# main_board.net
KiCad netlist of a schematic drawn in EAGLE
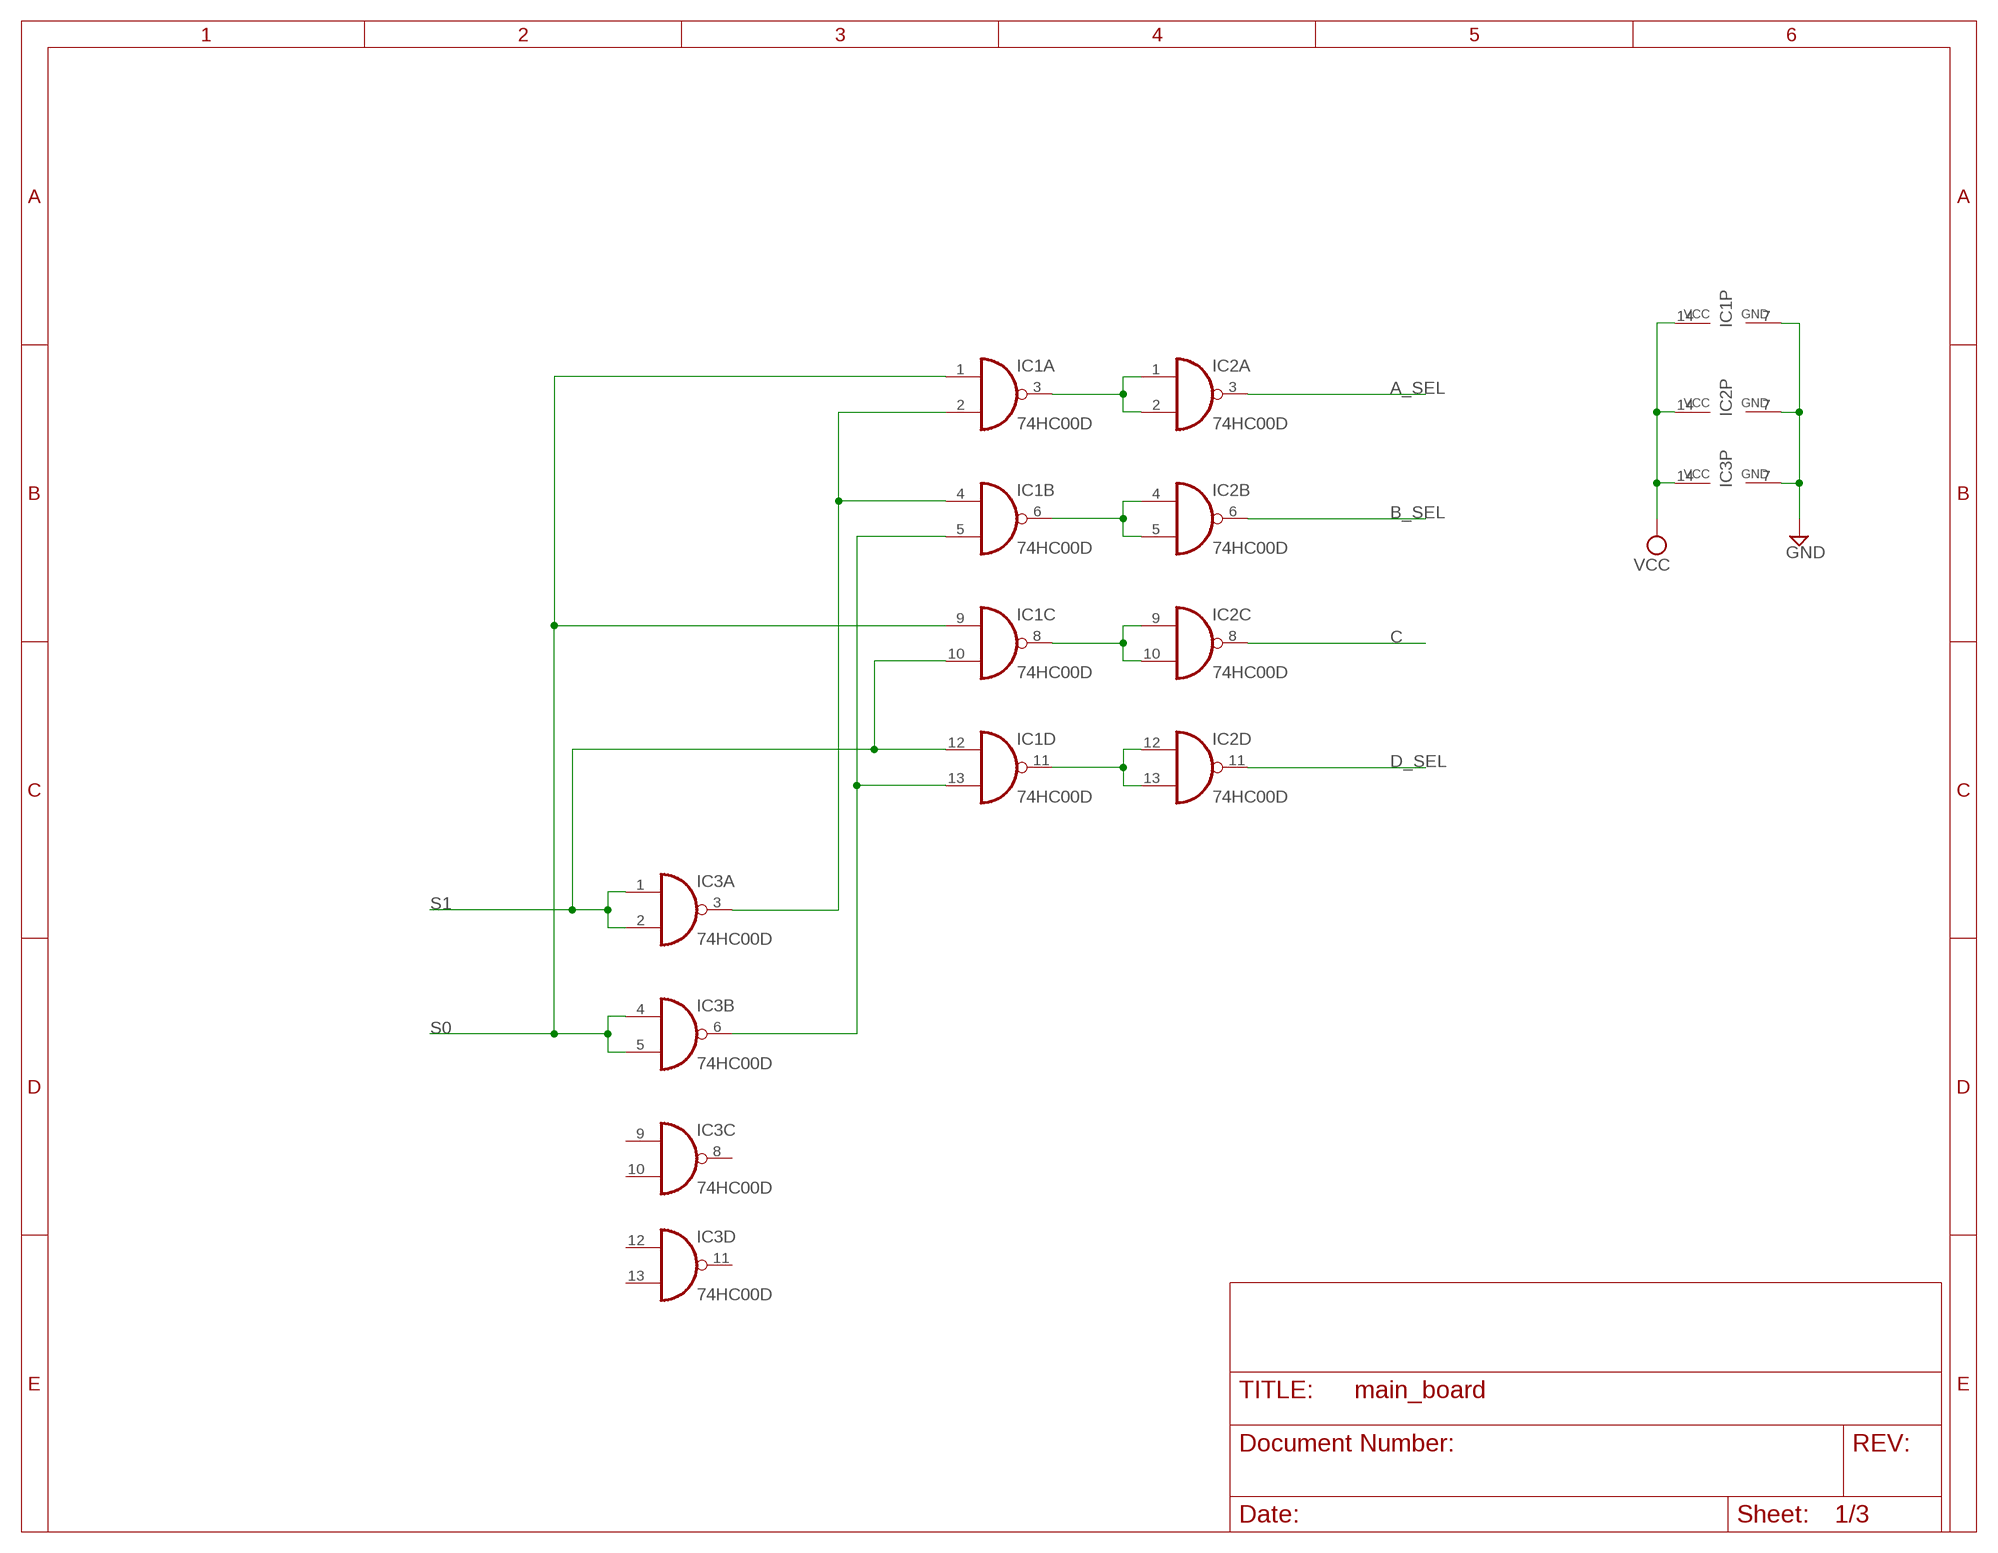
[diagram p0: schematic, sheet 1]
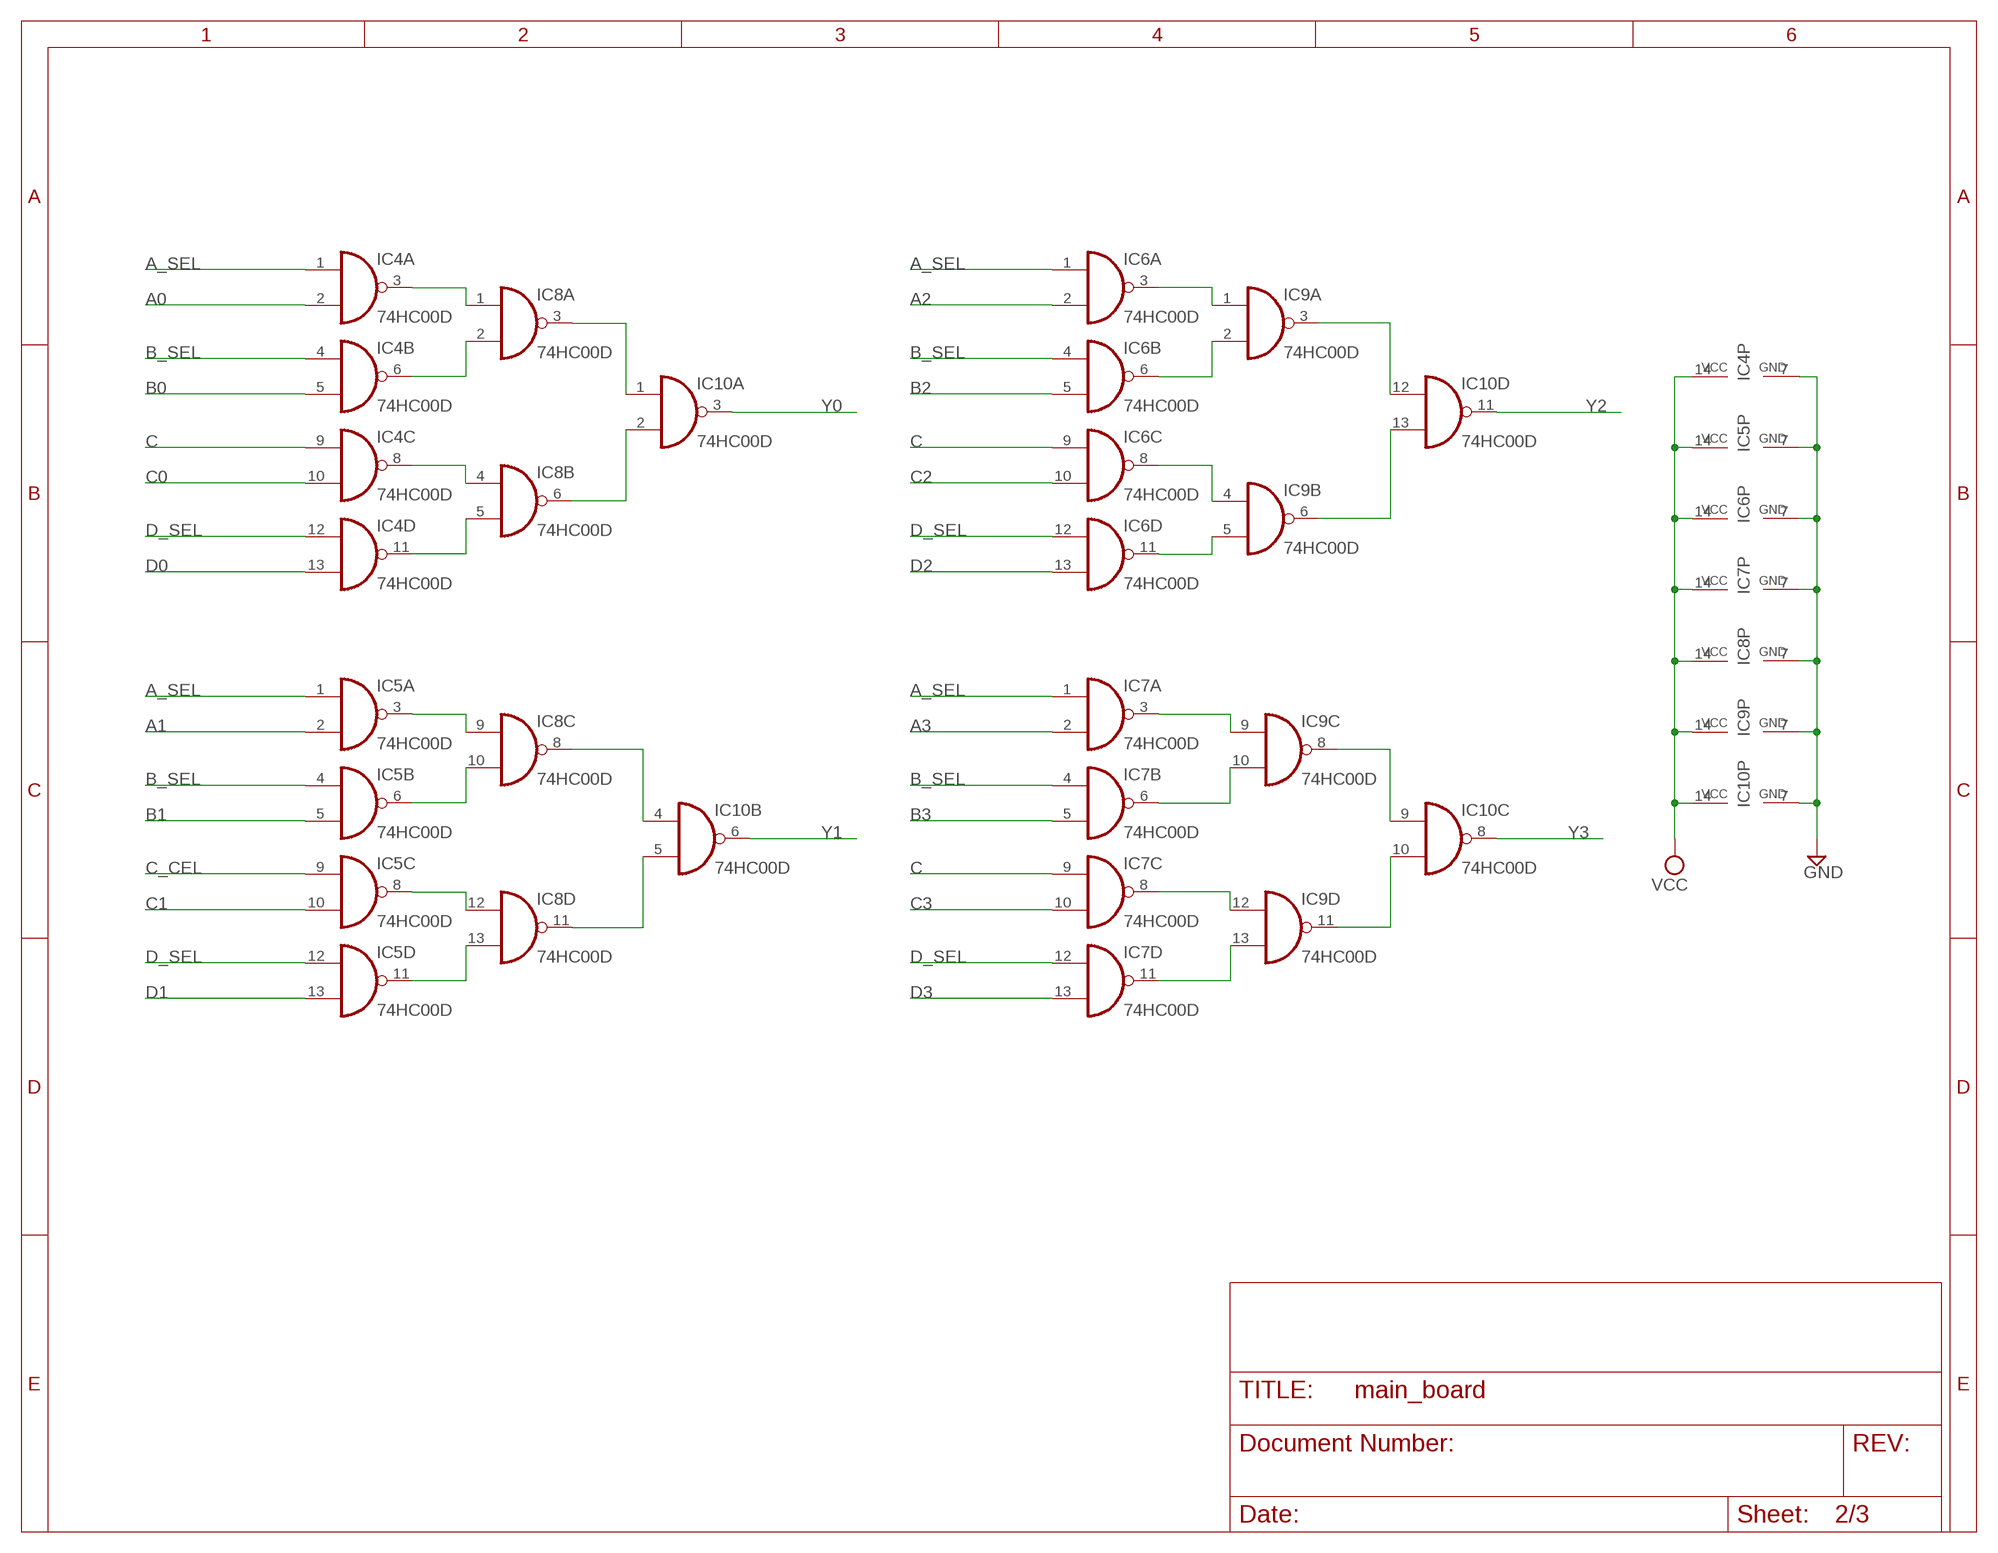
[diagram p1: schematic, sheet 2]
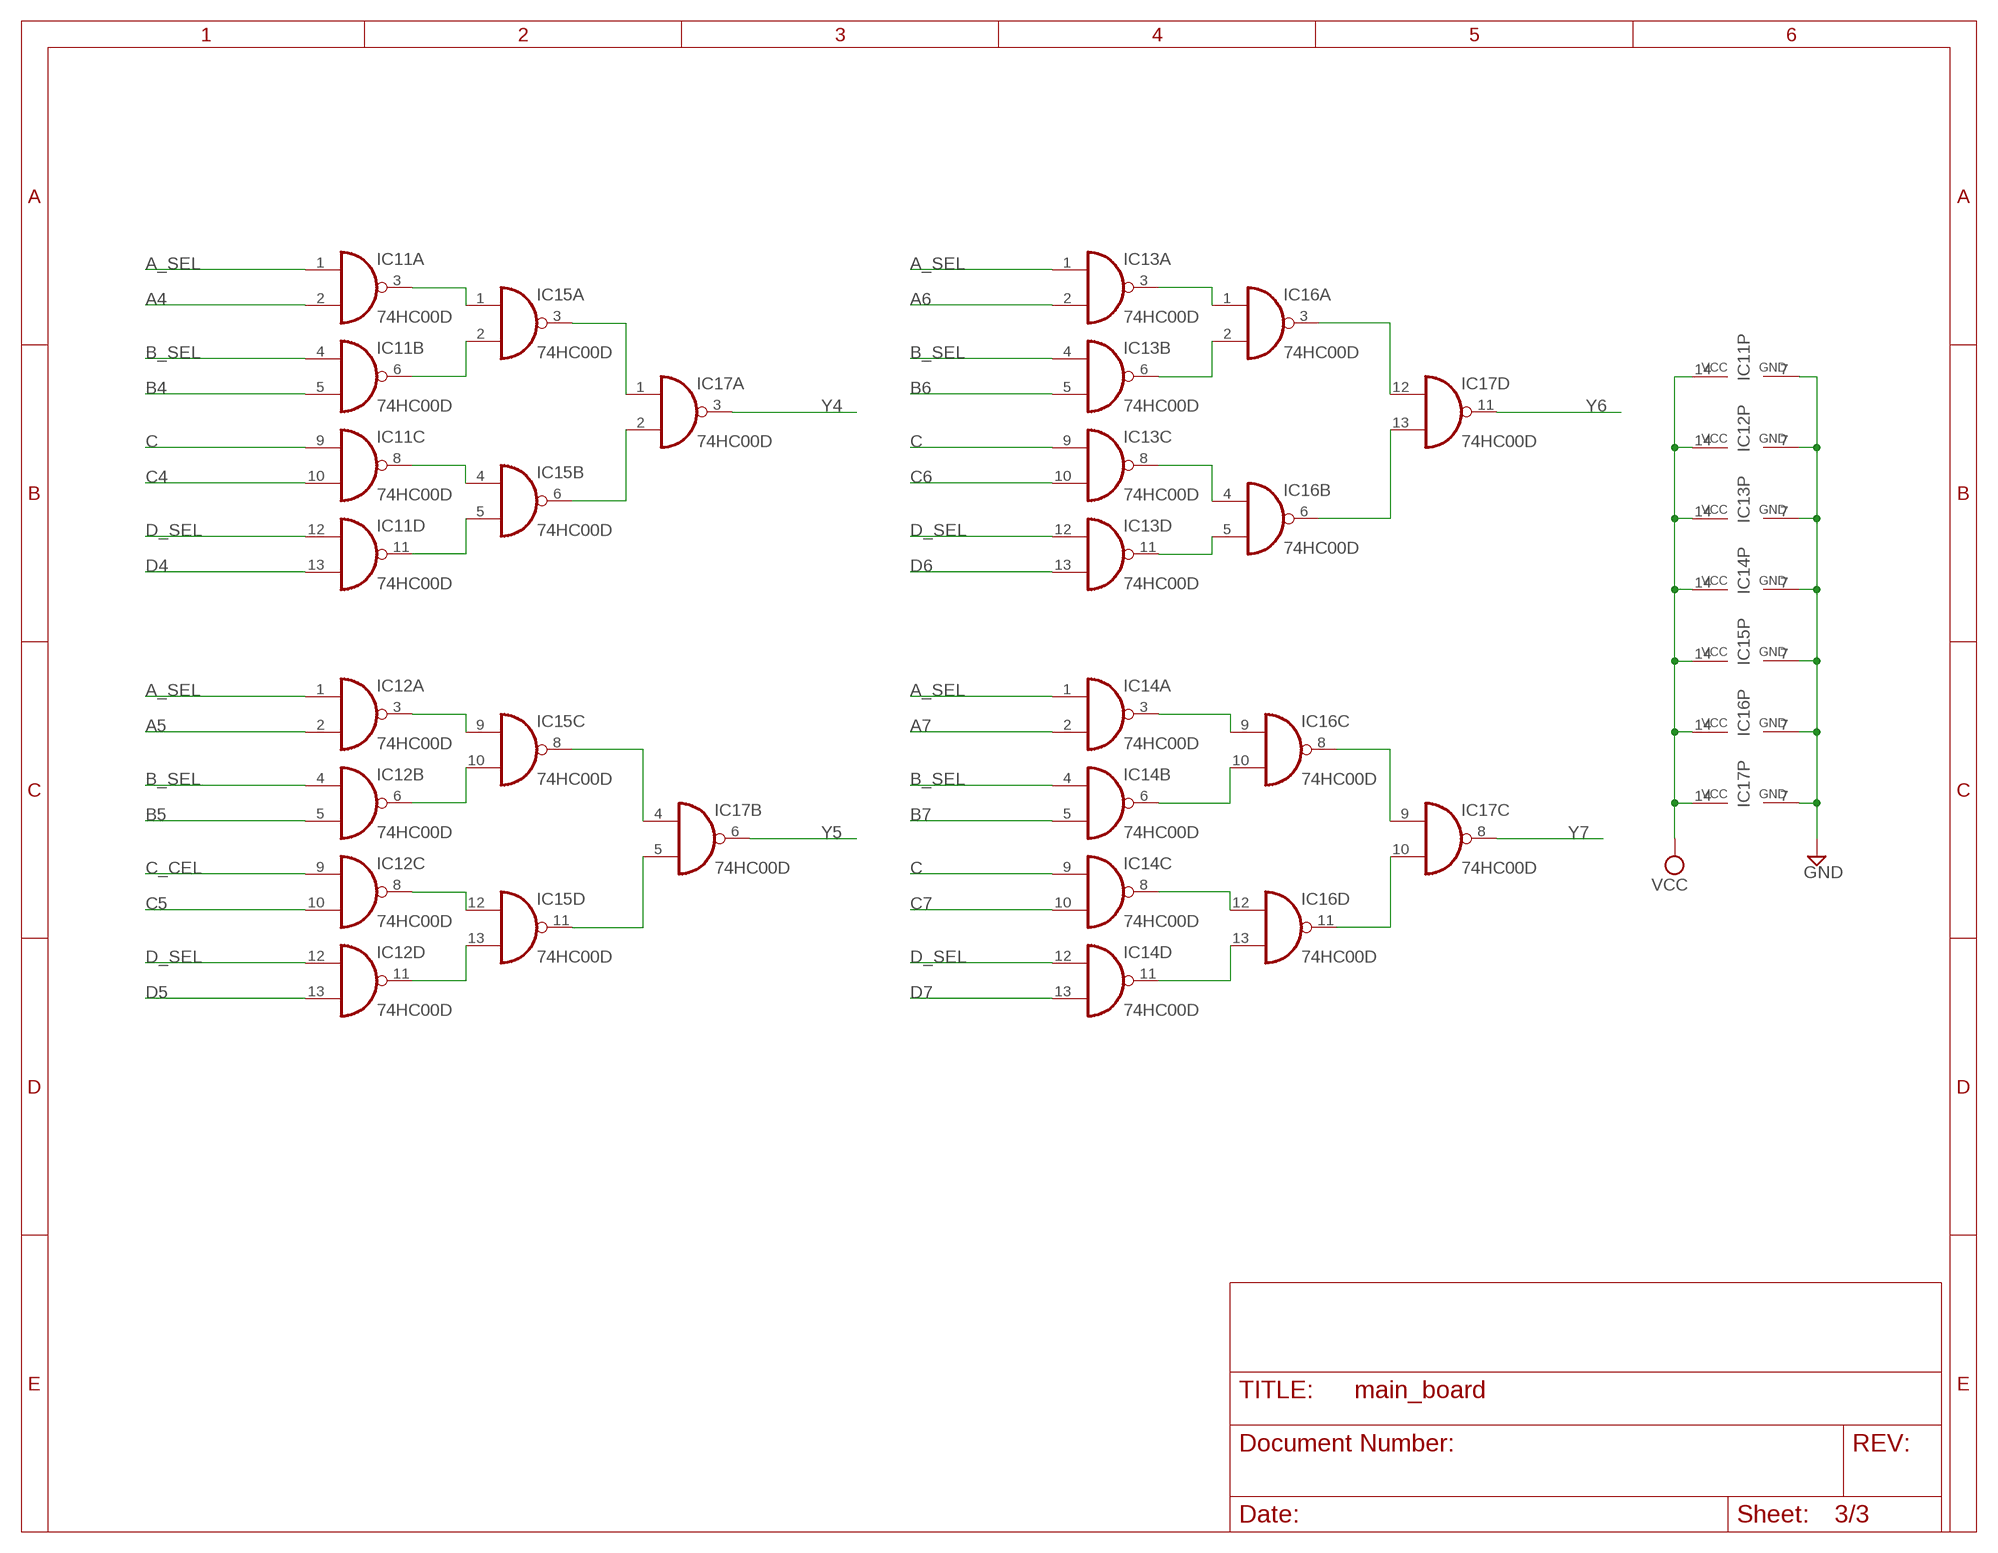
[diagram p2: schematic, sheet 3]

(export (version "E")
  (design (tool "Eeschema 10.0.6"))
  (components
    (comp (ref "IC4")
      (value "74HC00D")
      (footprint "eagle-import:SO14")
      (libsource (lib "eagle-import") (part "7400DHC"))
    )
    (comp (ref "IC5")
      (value "74HC00D")
      (footprint "eagle-import:SO14")
      (libsource (lib "eagle-import") (part "7400DHC"))
    )
    (comp (ref "IC6")
      (value "74HC00D")
      (footprint "eagle-import:SO14")
      (libsource (lib "eagle-import") (part "7400DHC"))
    )
    (comp (ref "IC7")
      (value "74HC00D")
      (footprint "eagle-import:SO14")
      (libsource (lib "eagle-import") (part "7400DHC"))
    )
    (comp (ref "IC8")
      (value "74HC00D")
      (footprint "eagle-import:SO14")
      (libsource (lib "eagle-import") (part "7400DHC"))
    )
    (comp (ref "IC9")
      (value "74HC00D")
      (footprint "eagle-import:SO14")
      (libsource (lib "eagle-import") (part "7400DHC"))
    )
    (comp (ref "IC10")
      (value "74HC00D")
      (footprint "eagle-import:SO14")
      (libsource (lib "eagle-import") (part "7400DHC"))
    )
    (comp (ref "IC1")
      (value "74HC00D")
      (footprint "eagle-import:SO14")
      (libsource (lib "eagle-import") (part "7400DHC"))
    )
    (comp (ref "IC2")
      (value "74HC00D")
      (footprint "eagle-import:SO14")
      (libsource (lib "eagle-import") (part "7400DHC"))
    )
    (comp (ref "IC3")
      (value "74HC00D")
      (footprint "eagle-import:SO14")
      (libsource (lib "eagle-import") (part "7400DHC"))
    )
    (comp (ref "IC11")
      (value "74HC00D")
      (footprint "eagle-import:SO14")
      (libsource (lib "eagle-import") (part "7400DHC"))
    )
    (comp (ref "IC12")
      (value "74HC00D")
      (footprint "eagle-import:SO14")
      (libsource (lib "eagle-import") (part "7400DHC"))
    )
    (comp (ref "IC13")
      (value "74HC00D")
      (footprint "eagle-import:SO14")
      (libsource (lib "eagle-import") (part "7400DHC"))
    )
    (comp (ref "IC14")
      (value "74HC00D")
      (footprint "eagle-import:SO14")
      (libsource (lib "eagle-import") (part "7400DHC"))
    )
    (comp (ref "IC15")
      (value "74HC00D")
      (footprint "eagle-import:SO14")
      (libsource (lib "eagle-import") (part "7400DHC"))
    )
    (comp (ref "IC16")
      (value "74HC00D")
      (footprint "eagle-import:SO14")
      (libsource (lib "eagle-import") (part "7400DHC"))
    )
    (comp (ref "IC17")
      (value "74HC00D")
      (footprint "eagle-import:SO14")
      (libsource (lib "eagle-import") (part "7400DHC"))
    )
  )
  (nets
    (net (code "1") (name "A0") (class "Default")
      (node (ref "IC4") (pin "2") (pinfunction "I1_2") (pintype "input"))
    )
    (net (code "2") (name "A1") (class "Default")
      (node (ref "IC5") (pin "2") (pinfunction "I1_2") (pintype "input"))
    )
    (net (code "3") (name "A2") (class "Default")
      (node (ref "IC6") (pin "2") (pinfunction "I1_2") (pintype "input"))
    )
    (net (code "4") (name "A3") (class "Default")
      (node (ref "IC7") (pin "2") (pinfunction "I1_2") (pintype "input"))
    )
    (net (code "5") (name "A4") (class "Default")
      (node (ref "IC11") (pin "2") (pinfunction "I1_2") (pintype "input"))
    )
    (net (code "6") (name "A5") (class "Default")
      (node (ref "IC12") (pin "2") (pinfunction "I1_2") (pintype "input"))
    )
    (net (code "7") (name "A6") (class "Default")
      (node (ref "IC13") (pin "2") (pinfunction "I1_2") (pintype "input"))
    )
    (net (code "8") (name "A7") (class "Default")
      (node (ref "IC14") (pin "2") (pinfunction "I1_2") (pintype "input"))
    )
    (net (code "9") (name "A_SEL") (class "Default")
      (node (ref "IC11") (pin "1") (pinfunction "I0_1") (pintype "input"))
      (node (ref "IC12") (pin "1") (pinfunction "I0_1") (pintype "input"))
      (node (ref "IC13") (pin "1") (pinfunction "I0_1") (pintype "input"))
      (node (ref "IC14") (pin "1") (pinfunction "I0_1") (pintype "input"))
      (node (ref "IC2") (pin "3") (pinfunction "O_3") (pintype "output"))
      (node (ref "IC4") (pin "1") (pinfunction "I0_1") (pintype "input"))
      (node (ref "IC5") (pin "1") (pinfunction "I0_1") (pintype "input"))
      (node (ref "IC6") (pin "1") (pinfunction "I0_1") (pintype "input"))
      (node (ref "IC7") (pin "1") (pinfunction "I0_1") (pintype "input"))
    )
    (net (code "10") (name "B0") (class "Default")
      (node (ref "IC4") (pin "5") (pinfunction "I1_5") (pintype "input"))
    )
    (net (code "11") (name "B1") (class "Default")
      (node (ref "IC5") (pin "5") (pinfunction "I1_5") (pintype "input"))
    )
    (net (code "12") (name "B2") (class "Default")
      (node (ref "IC6") (pin "5") (pinfunction "I1_5") (pintype "input"))
    )
    (net (code "13") (name "B3") (class "Default")
      (node (ref "IC7") (pin "5") (pinfunction "I1_5") (pintype "input"))
    )
    (net (code "14") (name "B4") (class "Default")
      (node (ref "IC11") (pin "5") (pinfunction "I1_5") (pintype "input"))
    )
    (net (code "15") (name "B5") (class "Default")
      (node (ref "IC12") (pin "5") (pinfunction "I1_5") (pintype "input"))
    )
    (net (code "16") (name "B6") (class "Default")
      (node (ref "IC13") (pin "5") (pinfunction "I1_5") (pintype "input"))
    )
    (net (code "17") (name "B7") (class "Default")
      (node (ref "IC14") (pin "5") (pinfunction "I1_5") (pintype "input"))
    )
    (net (code "18") (name "B_SEL") (class "Default")
      (node (ref "IC11") (pin "4") (pinfunction "I0_4") (pintype "input"))
      (node (ref "IC12") (pin "4") (pinfunction "I0_4") (pintype "input"))
      (node (ref "IC13") (pin "4") (pinfunction "I0_4") (pintype "input"))
      (node (ref "IC14") (pin "4") (pinfunction "I0_4") (pintype "input"))
      (node (ref "IC2") (pin "6") (pinfunction "O_6") (pintype "output"))
      (node (ref "IC4") (pin "4") (pinfunction "I0_4") (pintype "input"))
      (node (ref "IC5") (pin "4") (pinfunction "I0_4") (pintype "input"))
      (node (ref "IC6") (pin "4") (pinfunction "I0_4") (pintype "input"))
      (node (ref "IC7") (pin "4") (pinfunction "I0_4") (pintype "input"))
    )
    (net (code "19") (name "C") (class "Default")
      (node (ref "IC11") (pin "9") (pinfunction "I0_9") (pintype "input"))
      (node (ref "IC13") (pin "9") (pinfunction "I0_9") (pintype "input"))
      (node (ref "IC14") (pin "9") (pinfunction "I0_9") (pintype "input"))
      (node (ref "IC2") (pin "8") (pinfunction "O_8") (pintype "output"))
      (node (ref "IC4") (pin "9") (pinfunction "I0_9") (pintype "input"))
      (node (ref "IC6") (pin "9") (pinfunction "I0_9") (pintype "input"))
      (node (ref "IC7") (pin "9") (pinfunction "I0_9") (pintype "input"))
    )
    (net (code "20") (name "C0") (class "Default")
      (node (ref "IC4") (pin "10") (pinfunction "I1_10") (pintype "input"))
    )
    (net (code "21") (name "C1") (class "Default")
      (node (ref "IC5") (pin "10") (pinfunction "I1_10") (pintype "input"))
    )
    (net (code "22") (name "C2") (class "Default")
      (node (ref "IC6") (pin "10") (pinfunction "I1_10") (pintype "input"))
    )
    (net (code "23") (name "C3") (class "Default")
      (node (ref "IC7") (pin "10") (pinfunction "I1_10") (pintype "input"))
    )
    (net (code "24") (name "C4") (class "Default")
      (node (ref "IC11") (pin "10") (pinfunction "I1_10") (pintype "input"))
    )
    (net (code "25") (name "C5") (class "Default")
      (node (ref "IC12") (pin "10") (pinfunction "I1_10") (pintype "input"))
    )
    (net (code "26") (name "C6") (class "Default")
      (node (ref "IC13") (pin "10") (pinfunction "I1_10") (pintype "input"))
    )
    (net (code "27") (name "C7") (class "Default")
      (node (ref "IC14") (pin "10") (pinfunction "I1_10") (pintype "input"))
    )
    (net (code "28") (name "C_CEL") (class "Default")
      (node (ref "IC12") (pin "9") (pinfunction "I0_9") (pintype "input"))
      (node (ref "IC5") (pin "9") (pinfunction "I0_9") (pintype "input"))
    )
    (net (code "29") (name "D0") (class "Default")
      (node (ref "IC4") (pin "13") (pinfunction "I1_13") (pintype "input"))
    )
    (net (code "30") (name "D1") (class "Default")
      (node (ref "IC5") (pin "13") (pinfunction "I1_13") (pintype "input"))
    )
    (net (code "31") (name "D2") (class "Default")
      (node (ref "IC6") (pin "13") (pinfunction "I1_13") (pintype "input"))
    )
    (net (code "32") (name "D3") (class "Default")
      (node (ref "IC7") (pin "13") (pinfunction "I1_13") (pintype "input"))
    )
    (net (code "33") (name "D4") (class "Default")
      (node (ref "IC11") (pin "13") (pinfunction "I1_13") (pintype "input"))
    )
    (net (code "34") (name "D5") (class "Default")
      (node (ref "IC12") (pin "13") (pinfunction "I1_13") (pintype "input"))
    )
    (net (code "35") (name "D6") (class "Default")
      (node (ref "IC13") (pin "13") (pinfunction "I1_13") (pintype "input"))
    )
    (net (code "36") (name "D7") (class "Default")
      (node (ref "IC14") (pin "13") (pinfunction "I1_13") (pintype "input"))
    )
    (net (code "37") (name "D_SEL") (class "Default")
      (node (ref "IC11") (pin "12") (pinfunction "I0_12") (pintype "input"))
      (node (ref "IC12") (pin "12") (pinfunction "I0_12") (pintype "input"))
      (node (ref "IC13") (pin "12") (pinfunction "I0_12") (pintype "input"))
      (node (ref "IC14") (pin "12") (pinfunction "I0_12") (pintype "input"))
      (node (ref "IC2") (pin "11") (pinfunction "O_11") (pintype "output"))
      (node (ref "IC4") (pin "12") (pinfunction "I0_12") (pintype "input"))
      (node (ref "IC5") (pin "12") (pinfunction "I0_12") (pintype "input"))
      (node (ref "IC6") (pin "12") (pinfunction "I0_12") (pintype "input"))
      (node (ref "IC7") (pin "12") (pinfunction "I0_12") (pintype "input"))
    )
    (net (code "38") (name "GND") (class "Default")
      (node (ref "IC1") (pin "7") (pinfunction "GND_7") (pintype "power_in"))
      (node (ref "IC10") (pin "7") (pinfunction "GND_7") (pintype "power_in"))
      (node (ref "IC11") (pin "7") (pinfunction "GND_7") (pintype "power_in"))
      (node (ref "IC12") (pin "7") (pinfunction "GND_7") (pintype "power_in"))
      (node (ref "IC13") (pin "7") (pinfunction "GND_7") (pintype "power_in"))
      (node (ref "IC14") (pin "7") (pinfunction "GND_7") (pintype "power_in"))
      (node (ref "IC15") (pin "7") (pinfunction "GND_7") (pintype "power_in"))
      (node (ref "IC16") (pin "7") (pinfunction "GND_7") (pintype "power_in"))
      (node (ref "IC17") (pin "7") (pinfunction "GND_7") (pintype "power_in"))
      (node (ref "IC2") (pin "7") (pinfunction "GND_7") (pintype "power_in"))
      (node (ref "IC3") (pin "7") (pinfunction "GND_7") (pintype "power_in"))
      (node (ref "IC4") (pin "7") (pinfunction "GND_7") (pintype "power_in"))
      (node (ref "IC5") (pin "7") (pinfunction "GND_7") (pintype "power_in"))
      (node (ref "IC6") (pin "7") (pinfunction "GND_7") (pintype "power_in"))
      (node (ref "IC7") (pin "7") (pinfunction "GND_7") (pintype "power_in"))
      (node (ref "IC8") (pin "7") (pinfunction "GND_7") (pintype "power_in"))
      (node (ref "IC9") (pin "7") (pinfunction "GND_7") (pintype "power_in"))
    )
    (net (code "39") (name "Net-(IC1A-I1)") (class "Default")
      (node (ref "IC1") (pin "2") (pinfunction "I1_2") (pintype "input"))
      (node (ref "IC1") (pin "4") (pinfunction "I0_4") (pintype "input"))
      (node (ref "IC3") (pin "3") (pinfunction "O_3") (pintype "output"))
    )
    (net (code "40") (name "Net-(IC1A-O)") (class "Default")
      (node (ref "IC1") (pin "3") (pinfunction "O_3") (pintype "output"))
      (node (ref "IC2") (pin "1") (pinfunction "I0_1") (pintype "input"))
      (node (ref "IC2") (pin "2") (pinfunction "I1_2") (pintype "input"))
    )
    (net (code "41") (name "Net-(IC1B-I1)") (class "Default")
      (node (ref "IC1") (pin "13") (pinfunction "I1_13") (pintype "input"))
      (node (ref "IC1") (pin "5") (pinfunction "I1_5") (pintype "input"))
      (node (ref "IC3") (pin "6") (pinfunction "O_6") (pintype "output"))
    )
    (net (code "42") (name "Net-(IC1B-O)") (class "Default")
      (node (ref "IC1") (pin "6") (pinfunction "O_6") (pintype "output"))
      (node (ref "IC2") (pin "4") (pinfunction "I0_4") (pintype "input"))
      (node (ref "IC2") (pin "5") (pinfunction "I1_5") (pintype "input"))
    )
    (net (code "43") (name "Net-(IC1C-O)") (class "Default")
      (node (ref "IC1") (pin "8") (pinfunction "O_8") (pintype "output"))
      (node (ref "IC2") (pin "10") (pinfunction "I1_10") (pintype "input"))
      (node (ref "IC2") (pin "9") (pinfunction "I0_9") (pintype "input"))
    )
    (net (code "44") (name "Net-(IC1D-O)") (class "Default")
      (node (ref "IC1") (pin "11") (pinfunction "O_11") (pintype "output"))
      (node (ref "IC2") (pin "12") (pinfunction "I0_12") (pintype "input"))
      (node (ref "IC2") (pin "13") (pinfunction "I1_13") (pintype "input"))
    )
    (net (code "45") (name "Net-(IC4A-O)") (class "Default")
      (node (ref "IC4") (pin "3") (pinfunction "O_3") (pintype "output"))
      (node (ref "IC8") (pin "1") (pinfunction "I0_1") (pintype "input"))
    )
    (net (code "46") (name "Net-(IC4B-O)") (class "Default")
      (node (ref "IC4") (pin "6") (pinfunction "O_6") (pintype "output"))
      (node (ref "IC8") (pin "2") (pinfunction "I1_2") (pintype "input"))
    )
    (net (code "47") (name "Net-(IC4C-O)") (class "Default")
      (node (ref "IC4") (pin "8") (pinfunction "O_8") (pintype "output"))
      (node (ref "IC8") (pin "4") (pinfunction "I0_4") (pintype "input"))
    )
    (net (code "48") (name "Net-(IC4D-O)") (class "Default")
      (node (ref "IC4") (pin "11") (pinfunction "O_11") (pintype "output"))
      (node (ref "IC8") (pin "5") (pinfunction "I1_5") (pintype "input"))
    )
    (net (code "49") (name "Net-(IC5A-O)") (class "Default")
      (node (ref "IC5") (pin "3") (pinfunction "O_3") (pintype "output"))
      (node (ref "IC8") (pin "9") (pinfunction "I0_9") (pintype "input"))
    )
    (net (code "50") (name "Net-(IC5B-O)") (class "Default")
      (node (ref "IC5") (pin "6") (pinfunction "O_6") (pintype "output"))
      (node (ref "IC8") (pin "10") (pinfunction "I1_10") (pintype "input"))
    )
    (net (code "51") (name "Net-(IC5C-O)") (class "Default")
      (node (ref "IC5") (pin "8") (pinfunction "O_8") (pintype "output"))
      (node (ref "IC8") (pin "12") (pinfunction "I0_12") (pintype "input"))
    )
    (net (code "52") (name "Net-(IC5D-O)") (class "Default")
      (node (ref "IC5") (pin "11") (pinfunction "O_11") (pintype "output"))
      (node (ref "IC8") (pin "13") (pinfunction "I1_13") (pintype "input"))
    )
    (net (code "53") (name "Net-(IC6A-O)") (class "Default")
      (node (ref "IC6") (pin "3") (pinfunction "O_3") (pintype "output"))
      (node (ref "IC9") (pin "1") (pinfunction "I0_1") (pintype "input"))
    )
    (net (code "54") (name "Net-(IC6B-O)") (class "Default")
      (node (ref "IC6") (pin "6") (pinfunction "O_6") (pintype "output"))
      (node (ref "IC9") (pin "2") (pinfunction "I1_2") (pintype "input"))
    )
    (net (code "55") (name "Net-(IC6C-O)") (class "Default")
      (node (ref "IC6") (pin "8") (pinfunction "O_8") (pintype "output"))
      (node (ref "IC9") (pin "4") (pinfunction "I0_4") (pintype "input"))
    )
    (net (code "56") (name "Net-(IC6D-O)") (class "Default")
      (node (ref "IC6") (pin "11") (pinfunction "O_11") (pintype "output"))
      (node (ref "IC9") (pin "5") (pinfunction "I1_5") (pintype "input"))
    )
    (net (code "57") (name "Net-(IC7A-O)") (class "Default")
      (node (ref "IC7") (pin "3") (pinfunction "O_3") (pintype "output"))
      (node (ref "IC9") (pin "9") (pinfunction "I0_9") (pintype "input"))
    )
    (net (code "58") (name "Net-(IC7B-O)") (class "Default")
      (node (ref "IC7") (pin "6") (pinfunction "O_6") (pintype "output"))
      (node (ref "IC9") (pin "10") (pinfunction "I1_10") (pintype "input"))
    )
    (net (code "59") (name "Net-(IC7C-O)") (class "Default")
      (node (ref "IC7") (pin "8") (pinfunction "O_8") (pintype "output"))
      (node (ref "IC9") (pin "12") (pinfunction "I0_12") (pintype "input"))
    )
    (net (code "60") (name "Net-(IC7D-O)") (class "Default")
      (node (ref "IC7") (pin "11") (pinfunction "O_11") (pintype "output"))
      (node (ref "IC9") (pin "13") (pinfunction "I1_13") (pintype "input"))
    )
    (net (code "61") (name "Net-(IC10A-I0)") (class "Default")
      (node (ref "IC10") (pin "1") (pinfunction "I0_1") (pintype "input"))
      (node (ref "IC8") (pin "3") (pinfunction "O_3") (pintype "output"))
    )
    (net (code "62") (name "Net-(IC10A-I1)") (class "Default")
      (node (ref "IC10") (pin "2") (pinfunction "I1_2") (pintype "input"))
      (node (ref "IC8") (pin "6") (pinfunction "O_6") (pintype "output"))
    )
    (net (code "63") (name "Net-(IC10B-I0)") (class "Default")
      (node (ref "IC10") (pin "4") (pinfunction "I0_4") (pintype "input"))
      (node (ref "IC8") (pin "8") (pinfunction "O_8") (pintype "output"))
    )
    (net (code "64") (name "Net-(IC10B-I1)") (class "Default")
      (node (ref "IC10") (pin "5") (pinfunction "I1_5") (pintype "input"))
      (node (ref "IC8") (pin "11") (pinfunction "O_11") (pintype "output"))
    )
    (net (code "65") (name "Net-(IC10C-I0)") (class "Default")
      (node (ref "IC10") (pin "9") (pinfunction "I0_9") (pintype "input"))
      (node (ref "IC9") (pin "8") (pinfunction "O_8") (pintype "output"))
    )
    (net (code "66") (name "Net-(IC10C-I1)") (class "Default")
      (node (ref "IC10") (pin "10") (pinfunction "I1_10") (pintype "input"))
      (node (ref "IC9") (pin "11") (pinfunction "O_11") (pintype "output"))
    )
    (net (code "67") (name "Net-(IC10D-I0)") (class "Default")
      (node (ref "IC10") (pin "12") (pinfunction "I0_12") (pintype "input"))
      (node (ref "IC9") (pin "3") (pinfunction "O_3") (pintype "output"))
    )
    (net (code "68") (name "Net-(IC10D-I1)") (class "Default")
      (node (ref "IC10") (pin "13") (pinfunction "I1_13") (pintype "input"))
      (node (ref "IC9") (pin "6") (pinfunction "O_6") (pintype "output"))
    )
    (net (code "69") (name "Net-(IC11A-O)") (class "Default")
      (node (ref "IC11") (pin "3") (pinfunction "O_3") (pintype "output"))
      (node (ref "IC15") (pin "1") (pinfunction "I0_1") (pintype "input"))
    )
    (net (code "70") (name "Net-(IC11B-O)") (class "Default")
      (node (ref "IC11") (pin "6") (pinfunction "O_6") (pintype "output"))
      (node (ref "IC15") (pin "2") (pinfunction "I1_2") (pintype "input"))
    )
    (net (code "71") (name "Net-(IC11C-O)") (class "Default")
      (node (ref "IC11") (pin "8") (pinfunction "O_8") (pintype "output"))
      (node (ref "IC15") (pin "4") (pinfunction "I0_4") (pintype "input"))
    )
    (net (code "72") (name "Net-(IC11D-O)") (class "Default")
      (node (ref "IC11") (pin "11") (pinfunction "O_11") (pintype "output"))
      (node (ref "IC15") (pin "5") (pinfunction "I1_5") (pintype "input"))
    )
    (net (code "73") (name "Net-(IC12A-O)") (class "Default")
      (node (ref "IC12") (pin "3") (pinfunction "O_3") (pintype "output"))
      (node (ref "IC15") (pin "9") (pinfunction "I0_9") (pintype "input"))
    )
    (net (code "74") (name "Net-(IC12B-O)") (class "Default")
      (node (ref "IC12") (pin "6") (pinfunction "O_6") (pintype "output"))
      (node (ref "IC15") (pin "10") (pinfunction "I1_10") (pintype "input"))
    )
    (net (code "75") (name "Net-(IC12C-O)") (class "Default")
      (node (ref "IC12") (pin "8") (pinfunction "O_8") (pintype "output"))
      (node (ref "IC15") (pin "12") (pinfunction "I0_12") (pintype "input"))
    )
    (net (code "76") (name "Net-(IC12D-O)") (class "Default")
      (node (ref "IC12") (pin "11") (pinfunction "O_11") (pintype "output"))
      (node (ref "IC15") (pin "13") (pinfunction "I1_13") (pintype "input"))
    )
    (net (code "77") (name "Net-(IC13A-O)") (class "Default")
      (node (ref "IC13") (pin "3") (pinfunction "O_3") (pintype "output"))
      (node (ref "IC16") (pin "1") (pinfunction "I0_1") (pintype "input"))
    )
    (net (code "78") (name "Net-(IC13B-O)") (class "Default")
      (node (ref "IC13") (pin "6") (pinfunction "O_6") (pintype "output"))
      (node (ref "IC16") (pin "2") (pinfunction "I1_2") (pintype "input"))
    )
    (net (code "79") (name "Net-(IC13C-O)") (class "Default")
      (node (ref "IC13") (pin "8") (pinfunction "O_8") (pintype "output"))
      (node (ref "IC16") (pin "4") (pinfunction "I0_4") (pintype "input"))
    )
    (net (code "80") (name "Net-(IC13D-O)") (class "Default")
      (node (ref "IC13") (pin "11") (pinfunction "O_11") (pintype "output"))
      (node (ref "IC16") (pin "5") (pinfunction "I1_5") (pintype "input"))
    )
    (net (code "81") (name "Net-(IC14A-O)") (class "Default")
      (node (ref "IC14") (pin "3") (pinfunction "O_3") (pintype "output"))
      (node (ref "IC16") (pin "9") (pinfunction "I0_9") (pintype "input"))
    )
    (net (code "82") (name "Net-(IC14B-O)") (class "Default")
      (node (ref "IC14") (pin "6") (pinfunction "O_6") (pintype "output"))
      (node (ref "IC16") (pin "10") (pinfunction "I1_10") (pintype "input"))
    )
    (net (code "83") (name "Net-(IC14C-O)") (class "Default")
      (node (ref "IC14") (pin "8") (pinfunction "O_8") (pintype "output"))
      (node (ref "IC16") (pin "12") (pinfunction "I0_12") (pintype "input"))
    )
    (net (code "84") (name "Net-(IC14D-O)") (class "Default")
      (node (ref "IC14") (pin "11") (pinfunction "O_11") (pintype "output"))
      (node (ref "IC16") (pin "13") (pinfunction "I1_13") (pintype "input"))
    )
    (net (code "85") (name "Net-(IC15A-O)") (class "Default")
      (node (ref "IC15") (pin "3") (pinfunction "O_3") (pintype "output"))
      (node (ref "IC17") (pin "1") (pinfunction "I0_1") (pintype "input"))
    )
    (net (code "86") (name "Net-(IC15B-O)") (class "Default")
      (node (ref "IC15") (pin "6") (pinfunction "O_6") (pintype "output"))
      (node (ref "IC17") (pin "2") (pinfunction "I1_2") (pintype "input"))
    )
    (net (code "87") (name "Net-(IC15C-O)") (class "Default")
      (node (ref "IC15") (pin "8") (pinfunction "O_8") (pintype "output"))
      (node (ref "IC17") (pin "4") (pinfunction "I0_4") (pintype "input"))
    )
    (net (code "88") (name "Net-(IC15D-O)") (class "Default")
      (node (ref "IC15") (pin "11") (pinfunction "O_11") (pintype "output"))
      (node (ref "IC17") (pin "5") (pinfunction "I1_5") (pintype "input"))
    )
    (net (code "89") (name "Net-(IC16A-O)") (class "Default")
      (node (ref "IC16") (pin "3") (pinfunction "O_3") (pintype "output"))
      (node (ref "IC17") (pin "12") (pinfunction "I0_12") (pintype "input"))
    )
    (net (code "90") (name "Net-(IC16B-O)") (class "Default")
      (node (ref "IC16") (pin "6") (pinfunction "O_6") (pintype "output"))
      (node (ref "IC17") (pin "13") (pinfunction "I1_13") (pintype "input"))
    )
    (net (code "91") (name "Net-(IC16C-O)") (class "Default")
      (node (ref "IC16") (pin "8") (pinfunction "O_8") (pintype "output"))
      (node (ref "IC17") (pin "9") (pinfunction "I0_9") (pintype "input"))
    )
    (net (code "92") (name "Net-(IC16D-O)") (class "Default")
      (node (ref "IC16") (pin "11") (pinfunction "O_11") (pintype "output"))
      (node (ref "IC17") (pin "10") (pinfunction "I1_10") (pintype "input"))
    )
    (net (code "93") (name "S0") (class "Default")
      (node (ref "IC1") (pin "1") (pinfunction "I0_1") (pintype "input"))
      (node (ref "IC1") (pin "9") (pinfunction "I0_9") (pintype "input"))
      (node (ref "IC3") (pin "4") (pinfunction "I0_4") (pintype "input"))
      (node (ref "IC3") (pin "5") (pinfunction "I1_5") (pintype "input"))
    )
    (net (code "94") (name "S1") (class "Default")
      (node (ref "IC1") (pin "10") (pinfunction "I1_10") (pintype "input"))
      (node (ref "IC1") (pin "12") (pinfunction "I0_12") (pintype "input"))
      (node (ref "IC3") (pin "1") (pinfunction "I0_1") (pintype "input"))
      (node (ref "IC3") (pin "2") (pinfunction "I1_2") (pintype "input"))
    )
    (net (code "95") (name "VCC") (class "Default")
      (node (ref "IC1") (pin "14") (pinfunction "VCC_14") (pintype "power_in"))
      (node (ref "IC10") (pin "14") (pinfunction "VCC_14") (pintype "power_in"))
      (node (ref "IC11") (pin "14") (pinfunction "VCC_14") (pintype "power_in"))
      (node (ref "IC12") (pin "14") (pinfunction "VCC_14") (pintype "power_in"))
      (node (ref "IC13") (pin "14") (pinfunction "VCC_14") (pintype "power_in"))
      (node (ref "IC14") (pin "14") (pinfunction "VCC_14") (pintype "power_in"))
      (node (ref "IC15") (pin "14") (pinfunction "VCC_14") (pintype "power_in"))
      (node (ref "IC16") (pin "14") (pinfunction "VCC_14") (pintype "power_in"))
      (node (ref "IC17") (pin "14") (pinfunction "VCC_14") (pintype "power_in"))
      (node (ref "IC2") (pin "14") (pinfunction "VCC_14") (pintype "power_in"))
      (node (ref "IC3") (pin "14") (pinfunction "VCC_14") (pintype "power_in"))
      (node (ref "IC4") (pin "14") (pinfunction "VCC_14") (pintype "power_in"))
      (node (ref "IC5") (pin "14") (pinfunction "VCC_14") (pintype "power_in"))
      (node (ref "IC6") (pin "14") (pinfunction "VCC_14") (pintype "power_in"))
      (node (ref "IC7") (pin "14") (pinfunction "VCC_14") (pintype "power_in"))
      (node (ref "IC8") (pin "14") (pinfunction "VCC_14") (pintype "power_in"))
      (node (ref "IC9") (pin "14") (pinfunction "VCC_14") (pintype "power_in"))
    )
    (net (code "96") (name "Y0") (class "Default")
      (node (ref "IC10") (pin "3") (pinfunction "O_3") (pintype "output"))
    )
    (net (code "97") (name "Y1") (class "Default")
      (node (ref "IC10") (pin "6") (pinfunction "O_6") (pintype "output"))
    )
    (net (code "98") (name "Y2") (class "Default")
      (node (ref "IC10") (pin "11") (pinfunction "O_11") (pintype "output"))
    )
    (net (code "99") (name "Y3") (class "Default")
      (node (ref "IC10") (pin "8") (pinfunction "O_8") (pintype "output"))
    )
    (net (code "100") (name "Y4") (class "Default")
      (node (ref "IC17") (pin "3") (pinfunction "O_3") (pintype "output"))
    )
    (net (code "101") (name "Y5") (class "Default")
      (node (ref "IC17") (pin "6") (pinfunction "O_6") (pintype "output"))
    )
    (net (code "102") (name "Y6") (class "Default")
      (node (ref "IC17") (pin "11") (pinfunction "O_11") (pintype "output"))
    )
    (net (code "103") (name "Y7") (class "Default")
      (node (ref "IC17") (pin "8") (pinfunction "O_8") (pintype "output"))
    )
    (net (code "104") (name "unconnected-(IC3C-I0-Pad9)") (class "Default")
      (node (ref "IC3") (pin "9") (pinfunction "I0_9") (pintype "input"))
    )
    (net (code "105") (name "unconnected-(IC3C-I1-Pad10)") (class "Default")
      (node (ref "IC3") (pin "10") (pinfunction "I1_10") (pintype "input"))
    )
    (net (code "106") (name "unconnected-(IC3C-O-Pad8)") (class "Default")
      (node (ref "IC3") (pin "8") (pinfunction "O_8") (pintype "output"))
    )
    (net (code "107") (name "unconnected-(IC3D-I0-Pad12)") (class "Default")
      (node (ref "IC3") (pin "12") (pinfunction "I0_12") (pintype "input"))
    )
    (net (code "108") (name "unconnected-(IC3D-I1-Pad13)") (class "Default")
      (node (ref "IC3") (pin "13") (pinfunction "I1_13") (pintype "input"))
    )
    (net (code "109") (name "unconnected-(IC3D-O-Pad11)") (class "Default")
      (node (ref "IC3") (pin "11") (pinfunction "O_11") (pintype "output"))
    )
  )
)
